# design.net
KiCad netlist of a schematic drawn in Altium Designer
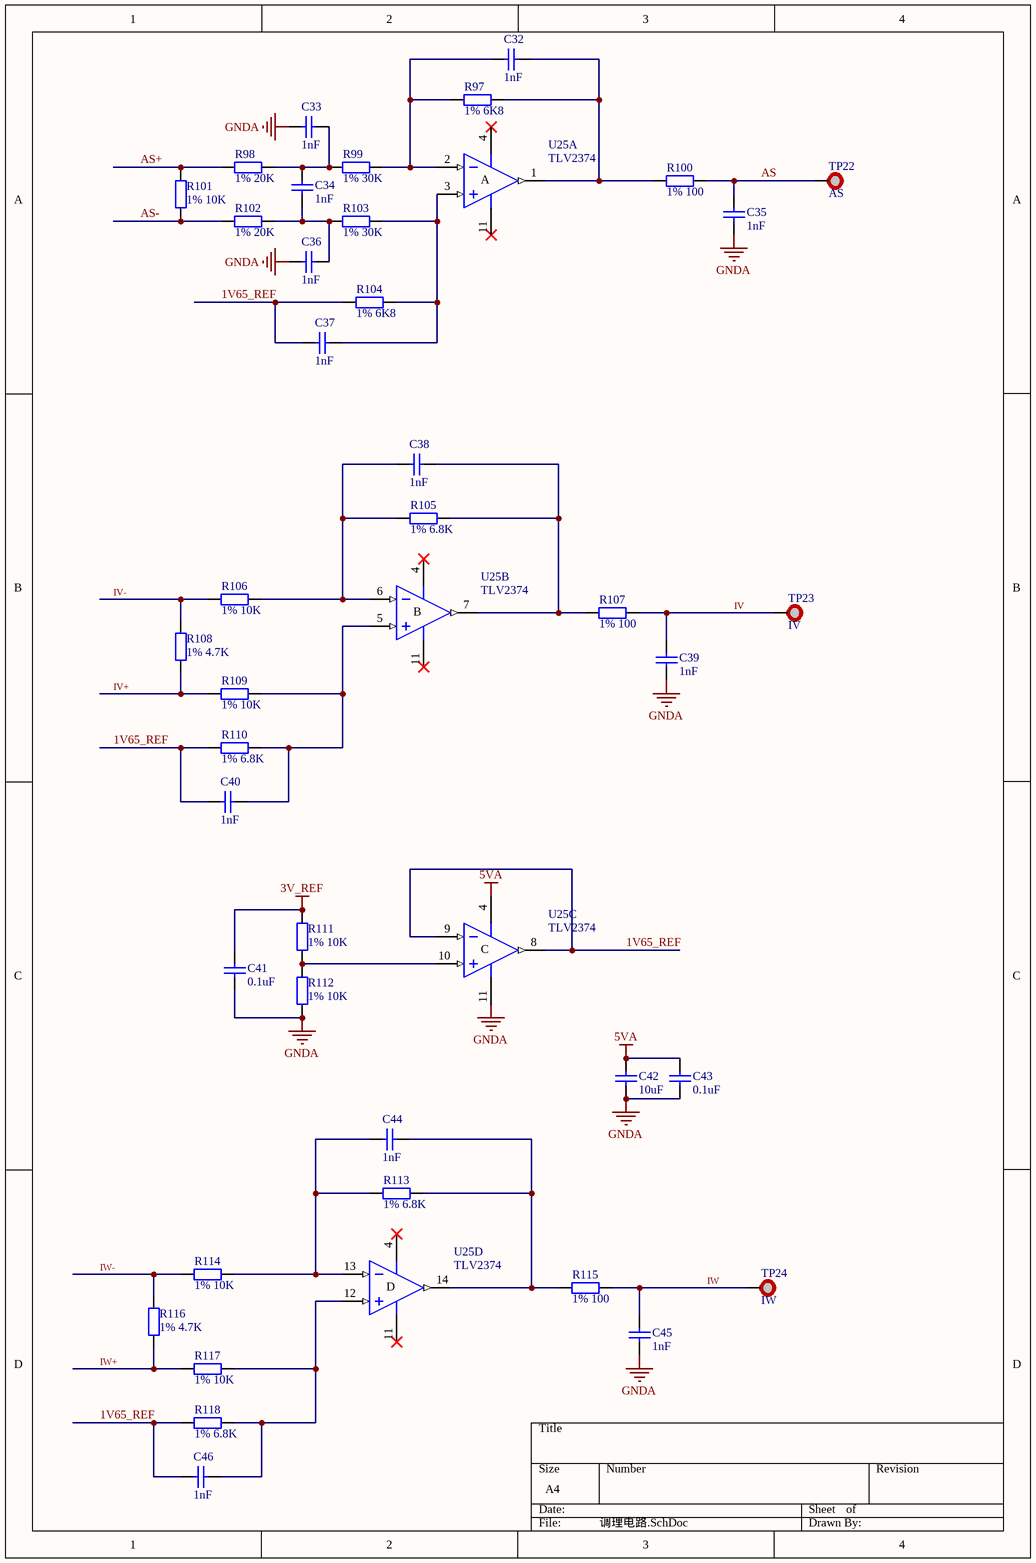
[diagram p0: 调理电路.SchDoc]

(export (version "E")
  (design (tool "Eeschema 10.0.6"))
  (components
    (comp (ref "C32")
      (value "1nF")
      (footprint "C SMD 0603")
      (description "Capacitor")
      (fields (field (name "PUBLISHER") "Altium Limited"))
      (libsource (lib "Miscellaneous Devices") (part "Cap"))
    )
    (comp (ref "C33")
      (value "1nF")
      (footprint "C SMD 0603")
      (description "Capacitor")
      (fields (field (name "PUBLISHER") "Altium Limited"))
      (libsource (lib "Miscellaneous Devices") (part "Cap"))
    )
    (comp (ref "C34")
      (value "1nF")
      (footprint "C SMD 0603")
      (description "Capacitor")
      (fields (field (name "PUBLISHER") "Altium Limited"))
      (libsource (lib "Miscellaneous Devices") (part "Cap"))
    )
    (comp (ref "C35")
      (value "1nF")
      (footprint "C SMD 0603")
      (description "Capacitor")
      (fields (field (name "PUBLISHER") "Altium Limited"))
      (libsource (lib "Miscellaneous Devices") (part "Cap"))
    )
    (comp (ref "C36")
      (value "1nF")
      (footprint "C SMD 0603")
      (description "Capacitor")
      (fields (field (name "PUBLISHER") "Altium Limited"))
      (libsource (lib "Miscellaneous Devices") (part "Cap"))
    )
    (comp (ref "C37")
      (value "1nF")
      (footprint "C SMD 0603")
      (description "Capacitor")
      (fields (field (name "PUBLISHER") "Altium Limited"))
      (libsource (lib "Miscellaneous Devices") (part "Cap"))
    )
    (comp (ref "C38")
      (value "1nF")
      (footprint "C SMD 0603")
      (description "Capacitor")
      (fields (field (name "PUBLISHER") "Altium Limited"))
      (libsource (lib "Miscellaneous Devices") (part "Cap"))
    )
    (comp (ref "C39")
      (value "1nF")
      (footprint "C SMD 0603")
      (description "Capacitor")
      (fields (field (name "PUBLISHER") "Altium Limited"))
      (libsource (lib "Miscellaneous Devices") (part "Cap"))
    )
    (comp (ref "C40")
      (value "1nF")
      (footprint "C SMD 0603")
      (description "Capacitor")
      (fields (field (name "PUBLISHER") "Altium Limited"))
      (libsource (lib "Miscellaneous Devices") (part "Cap"))
    )
    (comp (ref "C41")
      (value "0.1uF")
      (footprint "C SMD 0603")
      (description "Capacitor")
      (fields (field (name "PUBLISHER") "Altium Limited"))
      (libsource (lib "NCUC_PCB(V1.0)") (part "Cap"))
    )
    (comp (ref "C42")
      (value "10uF")
      (footprint "C SMD 1206")
      (description "Capacitor")
      (fields (field (name "PUBLISHER") "Altium Limited"))
      (libsource (lib "NCUC_PCB(V1.0)") (part "Cap"))
    )
    (comp (ref "C43")
      (value "0.1uF")
      (footprint "C SMD 0603")
      (description "Capacitor")
      (fields (field (name "PUBLISHER") "Altium Limited"))
      (libsource (lib "NCUC_PCB(V1.0)") (part "Cap"))
    )
    (comp (ref "C44")
      (value "1nF")
      (footprint "C SMD 0603")
      (description "Capacitor")
      (fields (field (name "PUBLISHER") "Altium Limited"))
      (libsource (lib "Miscellaneous Devices") (part "Cap"))
    )
    (comp (ref "C45")
      (value "1nF")
      (footprint "C SMD 0603")
      (description "Capacitor")
      (fields (field (name "PUBLISHER") "Altium Limited"))
      (libsource (lib "Miscellaneous Devices") (part "Cap"))
    )
    (comp (ref "C46")
      (value "1nF")
      (footprint "C SMD 0603")
      (description "Capacitor")
      (fields (field (name "PUBLISHER") "Altium Limited"))
      (libsource (lib "Miscellaneous Devices") (part "Cap"))
    )
    (comp (ref "R97")
      (value "1% 6K8")
      (footprint "R SMD 0603 1%")
      (description "Resistor")
      (fields (field (name "PUBLISHER") "Altium Limited"))
      (libsource (lib "Miscellaneous Devices") (part "Res2"))
    )
    (comp (ref "R98")
      (value "1% 20K")
      (footprint "R SMD 0603 1%")
      (description "Resistor")
      (fields (field (name "PUBLISHER") "Altium Limited"))
      (libsource (lib "Miscellaneous Devices") (part "Res2"))
    )
    (comp (ref "R99")
      (value "1% 30K")
      (footprint "R SMD 0603 1%")
      (description "Resistor")
      (fields (field (name "PUBLISHER") "Altium Limited"))
      (libsource (lib "Miscellaneous Devices") (part "Res2"))
    )
    (comp (ref "R100")
      (value "1% 100")
      (footprint "R SMD 0603 1%")
      (description "Resistor")
      (fields (field (name "PUBLISHER") "Altium Limited"))
      (libsource (lib "Miscellaneous Devices") (part "Res2"))
    )
    (comp (ref "R101")
      (value "1% 10K")
      (footprint "R SMD 0603 1%")
      (description "Resistor")
      (fields (field (name "PUBLISHER") "Altium Limited"))
      (libsource (lib "") (part "Res2_2"))
    )
    (comp (ref "R102")
      (value "1% 20K")
      (footprint "R SMD 0603 1%")
      (description "Resistor")
      (fields (field (name "PUBLISHER") "Altium Limited"))
      (libsource (lib "Miscellaneous Devices") (part "Res2"))
    )
    (comp (ref "R103")
      (value "1% 30K")
      (footprint "R SMD 0603 1%")
      (description "Resistor")
      (fields (field (name "PUBLISHER") "Altium Limited"))
      (libsource (lib "Miscellaneous Devices") (part "Res2"))
    )
    (comp (ref "R104")
      (value "1% 6K8")
      (footprint "R SMD 0603 1%")
      (description "Resistor")
      (fields (field (name "PUBLISHER") "Altium Limited"))
      (libsource (lib "Miscellaneous Devices") (part "Res2"))
    )
    (comp (ref "R105")
      (value "1% 6.8K")
      (footprint "R SMD 0603 1%")
      (description "Resistor")
      (fields (field (name "PUBLISHER") "Altium Limited"))
      (libsource (lib "") (part "Res2_1"))
    )
    (comp (ref "R106")
      (value "1% 10K")
      (footprint "R SMD 0603 1%")
      (description "Resistor")
      (fields (field (name "PUBLISHER") "Altium Limited"))
      (libsource (lib "") (part "Res2_1"))
    )
    (comp (ref "R107")
      (value "1% 100")
      (footprint "R SMD 0603 1%")
      (description "Resistor")
      (fields (field (name "PUBLISHER") "Altium Limited"))
      (libsource (lib "Miscellaneous Devices") (part "Res2"))
    )
    (comp (ref "R108")
      (value "1% 4.7K")
      (footprint "R SMD 0603 1%")
      (description "Resistor")
      (fields (field (name "PUBLISHER") "Altium Limited"))
      (libsource (lib "") (part "Res2_2"))
    )
    (comp (ref "R109")
      (value "1% 10K")
      (footprint "R SMD 0603 1%")
      (description "Resistor")
      (fields (field (name "PUBLISHER") "Altium Limited"))
      (libsource (lib "") (part "Res2_1"))
    )
    (comp (ref "R110")
      (value "1% 6.8K")
      (footprint "R SMD 0603 1%")
      (description "Resistor")
      (fields (field (name "PUBLISHER") "Altium Limited"))
      (libsource (lib "") (part "Res2_1"))
    )
    (comp (ref "R111")
      (value "1% 10K")
      (footprint "R SMD 0603 1%")
      (description "Resistor")
      (fields (field (name "PUBLISHER") "Altium Limited"))
      (libsource (lib "") (part "Res2_3"))
    )
    (comp (ref "R112")
      (value "1% 10K")
      (footprint "R SMD 0603 1%")
      (description "Resistor")
      (fields (field (name "PUBLISHER") "Altium Limited"))
      (libsource (lib "") (part "Res2_3"))
    )
    (comp (ref "R113")
      (value "1% 6.8K")
      (footprint "R SMD 0603 1%")
      (description "Resistor")
      (fields (field (name "PUBLISHER") "Altium Limited"))
      (libsource (lib "") (part "Res2_1"))
    )
    (comp (ref "R114")
      (value "1% 10K")
      (footprint "R SMD 0603 1%")
      (description "Resistor")
      (fields (field (name "PUBLISHER") "Altium Limited"))
      (libsource (lib "") (part "Res2_1"))
    )
    (comp (ref "R115")
      (value "1% 100")
      (footprint "R SMD 0603 1%")
      (description "Resistor")
      (fields (field (name "PUBLISHER") "Altium Limited"))
      (libsource (lib "Miscellaneous Devices") (part "Res2"))
    )
    (comp (ref "R116")
      (value "1% 4.7K")
      (footprint "R SMD 0603 1%")
      (description "Resistor")
      (fields (field (name "PUBLISHER") "Altium Limited"))
      (libsource (lib "") (part "Res2_2"))
    )
    (comp (ref "R117")
      (value "1% 10K")
      (footprint "R SMD 0603 1%")
      (description "Resistor")
      (fields (field (name "PUBLISHER") "Altium Limited"))
      (libsource (lib "") (part "Res2_1"))
    )
    (comp (ref "R118")
      (value "1% 6.8K")
      (footprint "R SMD 0603 1%")
      (description "Resistor")
      (fields (field (name "PUBLISHER") "Altium Limited"))
      (libsource (lib "") (part "Res2_1"))
    )
    (comp (ref "TP22") (value "AS") (footprint "测点") (libsource (lib "mysch") (part "TEST_POINT")))
    (comp (ref "TP23") (value "IV") (footprint "测点") (libsource (lib "mysch") (part "TEST_POINT")))
    (comp (ref "TP24") (value "IW") (footprint "测点") (libsource (lib "mysch") (part "TEST_POINT")))
    (comp (ref "U25")
      (value "TLV2374")
      (footprint "NSO14_N")
      (description "Low-Power, Precision FET-Input Operational Amplifiers")
      (fields (field (name "PUBLISHER") "Altium Limited"))
      (libsource (lib "BB Operational Amplifier") (part "TLV2374"))
    )
  )
  (nets
    (net (code "1") (name "/1V65_REF") (class "Default")
      (node (ref "C37") (pin "1") (pinfunction "1_1") (pintype "passive"))
      (node (ref "C40") (pin "1") (pinfunction "1_1") (pintype "passive"))
      (node (ref "C46") (pin "1") (pinfunction "1_1") (pintype "passive"))
      (node (ref "R104") (pin "1") (pinfunction "1_1") (pintype "passive"))
      (node (ref "R110") (pin "2") (pinfunction "2_2") (pintype "passive"))
      (node (ref "R118") (pin "2") (pinfunction "2_2") (pintype "passive"))
      (node (ref "U25") (pin "8") (pinfunction "OUT_8") (pintype "output"))
      (node (ref "U25") (pin "9") (pinfunction "IN-_9") (pintype "input"))
    )
    (net (code "2") (name "/AS") (class "Default")
      (node (ref "C35") (pin "2") (pinfunction "2_2") (pintype "passive"))
      (node (ref "R100") (pin "2") (pinfunction "2_2") (pintype "passive"))
      (node (ref "TP22") (pin "1") (pinfunction "1_1") (pintype "passive"))
    )
    (net (code "3") (name "/AS+") (class "Default")
      (node (ref "R101") (pin "1") (pinfunction "1_1") (pintype "passive"))
      (node (ref "R98") (pin "1") (pinfunction "1_1") (pintype "passive"))
    )
    (net (code "4") (name "/AS-") (class "Default")
      (node (ref "R101") (pin "2") (pinfunction "2_2") (pintype "passive"))
      (node (ref "R102") (pin "1") (pinfunction "1_1") (pintype "passive"))
    )
    (net (code "5") (name "/IV") (class "Default")
      (node (ref "C39") (pin "2") (pinfunction "2_2") (pintype "passive"))
      (node (ref "R107") (pin "2") (pinfunction "2_2") (pintype "passive"))
      (node (ref "TP23") (pin "1") (pinfunction "1_1") (pintype "passive"))
    )
    (net (code "6") (name "/IV+") (class "Default")
      (node (ref "R108") (pin "2") (pinfunction "2_2") (pintype "passive"))
      (node (ref "R109") (pin "2") (pinfunction "2_2") (pintype "passive"))
    )
    (net (code "7") (name "/IV-") (class "Default")
      (node (ref "R106") (pin "2") (pinfunction "2_2") (pintype "passive"))
      (node (ref "R108") (pin "1") (pinfunction "1_1") (pintype "passive"))
    )
    (net (code "8") (name "/IW") (class "Default")
      (node (ref "C45") (pin "2") (pinfunction "2_2") (pintype "passive"))
      (node (ref "R115") (pin "2") (pinfunction "2_2") (pintype "passive"))
      (node (ref "TP24") (pin "1") (pinfunction "1_1") (pintype "passive"))
    )
    (net (code "9") (name "/IW+") (class "Default")
      (node (ref "R116") (pin "2") (pinfunction "2_2") (pintype "passive"))
      (node (ref "R117") (pin "2") (pinfunction "2_2") (pintype "passive"))
    )
    (net (code "10") (name "/IW-") (class "Default")
      (node (ref "R114") (pin "2") (pinfunction "2_2") (pintype "passive"))
      (node (ref "R116") (pin "1") (pinfunction "1_1") (pintype "passive"))
    )
    (net (code "11") (name "3V_REF") (class "Default")
      (node (ref "C41") (pin "2") (pinfunction "2_2") (pintype "passive"))
      (node (ref "R111") (pin "2") (pinfunction "2_2") (pintype "passive"))
    )
    (net (code "12") (name "5VA") (class "Default")
      (node (ref "C42") (pin "2") (pinfunction "2_2") (pintype "passive"))
      (node (ref "C43") (pin "2") (pinfunction "2_2") (pintype "passive"))
      (node (ref "U25") (pin "4") (pinfunction "V+_4") (pintype "power_in"))
    )
    (net (code "13") (name "GNDA") (class "Default")
      (node (ref "C33") (pin "1") (pinfunction "1_1") (pintype "passive"))
      (node (ref "C35") (pin "1") (pinfunction "1_1") (pintype "passive"))
      (node (ref "C36") (pin "1") (pinfunction "1_1") (pintype "passive"))
      (node (ref "C39") (pin "1") (pinfunction "1_1") (pintype "passive"))
      (node (ref "C41") (pin "1") (pinfunction "1_1") (pintype "passive"))
      (node (ref "C42") (pin "1") (pinfunction "1_1") (pintype "passive"))
      (node (ref "C43") (pin "1") (pinfunction "1_1") (pintype "passive"))
      (node (ref "C45") (pin "1") (pinfunction "1_1") (pintype "passive"))
      (node (ref "R112") (pin "1") (pinfunction "1_1") (pintype "passive"))
      (node (ref "U25") (pin "11") (pinfunction "V-_11") (pintype "power_in"))
    )
    (net (code "14") (name "Net-(C33-Pad2)") (class "Default")
      (node (ref "C33") (pin "2") (pinfunction "2_2") (pintype "passive"))
      (node (ref "C34") (pin "1") (pinfunction "1_1") (pintype "passive"))
      (node (ref "R98") (pin "2") (pinfunction "2_2") (pintype "passive"))
      (node (ref "R99") (pin "1") (pinfunction "1_1") (pintype "passive"))
    )
    (net (code "15") (name "Net-(C34-Pad2)") (class "Default")
      (node (ref "C34") (pin "2") (pinfunction "2_2") (pintype "passive"))
      (node (ref "C36") (pin "2") (pinfunction "2_2") (pintype "passive"))
      (node (ref "R102") (pin "2") (pinfunction "2_2") (pintype "passive"))
      (node (ref "R103") (pin "1") (pinfunction "1_1") (pintype "passive"))
    )
    (net (code "16") (name "Net-(U25A-IN+)") (class "Default")
      (node (ref "C37") (pin "2") (pinfunction "2_2") (pintype "passive"))
      (node (ref "R103") (pin "2") (pinfunction "2_2") (pintype "passive"))
      (node (ref "R104") (pin "2") (pinfunction "2_2") (pintype "passive"))
      (node (ref "U25") (pin "3") (pinfunction "IN+_3") (pintype "input"))
    )
    (net (code "17") (name "Net-(U25A-IN-)") (class "Default")
      (node (ref "C32") (pin "1") (pinfunction "1_1") (pintype "passive"))
      (node (ref "R97") (pin "1") (pinfunction "1_1") (pintype "passive"))
      (node (ref "R99") (pin "2") (pinfunction "2_2") (pintype "passive"))
      (node (ref "U25") (pin "2") (pinfunction "IN-_2") (pintype "input"))
    )
    (net (code "18") (name "Net-(U25A-OUT)") (class "Default")
      (node (ref "C32") (pin "2") (pinfunction "2_2") (pintype "passive"))
      (node (ref "R100") (pin "1") (pinfunction "1_1") (pintype "passive"))
      (node (ref "R97") (pin "2") (pinfunction "2_2") (pintype "passive"))
      (node (ref "U25") (pin "1") (pinfunction "OUT_1") (pintype "output"))
    )
    (net (code "19") (name "Net-(U25B-IN+)") (class "Default")
      (node (ref "C40") (pin "2") (pinfunction "2_2") (pintype "passive"))
      (node (ref "R109") (pin "1") (pinfunction "1_1") (pintype "passive"))
      (node (ref "R110") (pin "1") (pinfunction "1_1") (pintype "passive"))
      (node (ref "U25") (pin "5") (pinfunction "IN+_5") (pintype "input"))
    )
    (net (code "20") (name "Net-(U25B-IN-)") (class "Default")
      (node (ref "C38") (pin "1") (pinfunction "1_1") (pintype "passive"))
      (node (ref "R105") (pin "2") (pinfunction "2_2") (pintype "passive"))
      (node (ref "R106") (pin "1") (pinfunction "1_1") (pintype "passive"))
      (node (ref "U25") (pin "6") (pinfunction "IN-_6") (pintype "input"))
    )
    (net (code "21") (name "Net-(U25B-OUT)") (class "Default")
      (node (ref "C38") (pin "2") (pinfunction "2_2") (pintype "passive"))
      (node (ref "R105") (pin "1") (pinfunction "1_1") (pintype "passive"))
      (node (ref "R107") (pin "1") (pinfunction "1_1") (pintype "passive"))
      (node (ref "U25") (pin "7") (pinfunction "OUT_7") (pintype "output"))
    )
    (net (code "22") (name "Net-(U25C-IN+)") (class "Default")
      (node (ref "R111") (pin "1") (pinfunction "1_1") (pintype "passive"))
      (node (ref "R112") (pin "2") (pinfunction "2_2") (pintype "passive"))
      (node (ref "U25") (pin "10") (pinfunction "IN+_10") (pintype "input"))
    )
    (net (code "23") (name "Net-(U25D-IN+)") (class "Default")
      (node (ref "C46") (pin "2") (pinfunction "2_2") (pintype "passive"))
      (node (ref "R117") (pin "1") (pinfunction "1_1") (pintype "passive"))
      (node (ref "R118") (pin "1") (pinfunction "1_1") (pintype "passive"))
      (node (ref "U25") (pin "12") (pinfunction "IN+_12") (pintype "input"))
    )
    (net (code "24") (name "Net-(U25D-IN-)") (class "Default")
      (node (ref "C44") (pin "1") (pinfunction "1_1") (pintype "passive"))
      (node (ref "R113") (pin "2") (pinfunction "2_2") (pintype "passive"))
      (node (ref "R114") (pin "1") (pinfunction "1_1") (pintype "passive"))
      (node (ref "U25") (pin "13") (pinfunction "IN-_13") (pintype "input"))
    )
    (net (code "25") (name "Net-(U25D-OUT)") (class "Default")
      (node (ref "C44") (pin "2") (pinfunction "2_2") (pintype "passive"))
      (node (ref "R113") (pin "1") (pinfunction "1_1") (pintype "passive"))
      (node (ref "R115") (pin "1") (pinfunction "1_1") (pintype "passive"))
      (node (ref "U25") (pin "14") (pinfunction "OUT_14") (pintype "output"))
    )
    (net (code "26") (name "unconnected-(U25A-V+-Pad4)") (class "Default")
      (node (ref "U25") (pin "4") (pinfunction "V+_4") (pintype "power_in+no_connect"))
    )
    (net (code "27") (name "unconnected-(U25A-V--Pad11)") (class "Default")
      (node (ref "U25") (pin "11") (pinfunction "V-_11") (pintype "power_in+no_connect"))
    )
    (net (code "28") (name "unconnected-(U25B-V+-Pad4)") (class "Default")
      (node (ref "U25") (pin "4") (pinfunction "V+_4") (pintype "power_in+no_connect"))
    )
    (net (code "29") (name "unconnected-(U25B-V--Pad11)") (class "Default")
      (node (ref "U25") (pin "11") (pinfunction "V-_11") (pintype "power_in+no_connect"))
    )
    (net (code "30") (name "unconnected-(U25D-V+-Pad4)") (class "Default")
      (node (ref "U25") (pin "4") (pinfunction "V+_4") (pintype "power_in+no_connect"))
    )
    (net (code "31") (name "unconnected-(U25D-V--Pad11)") (class "Default")
      (node (ref "U25") (pin "11") (pinfunction "V-_11") (pintype "power_in+no_connect"))
    )
  )
)
